# Main_Titan_V2.net
KiCad netlist of a schematic drawn in EAGLE
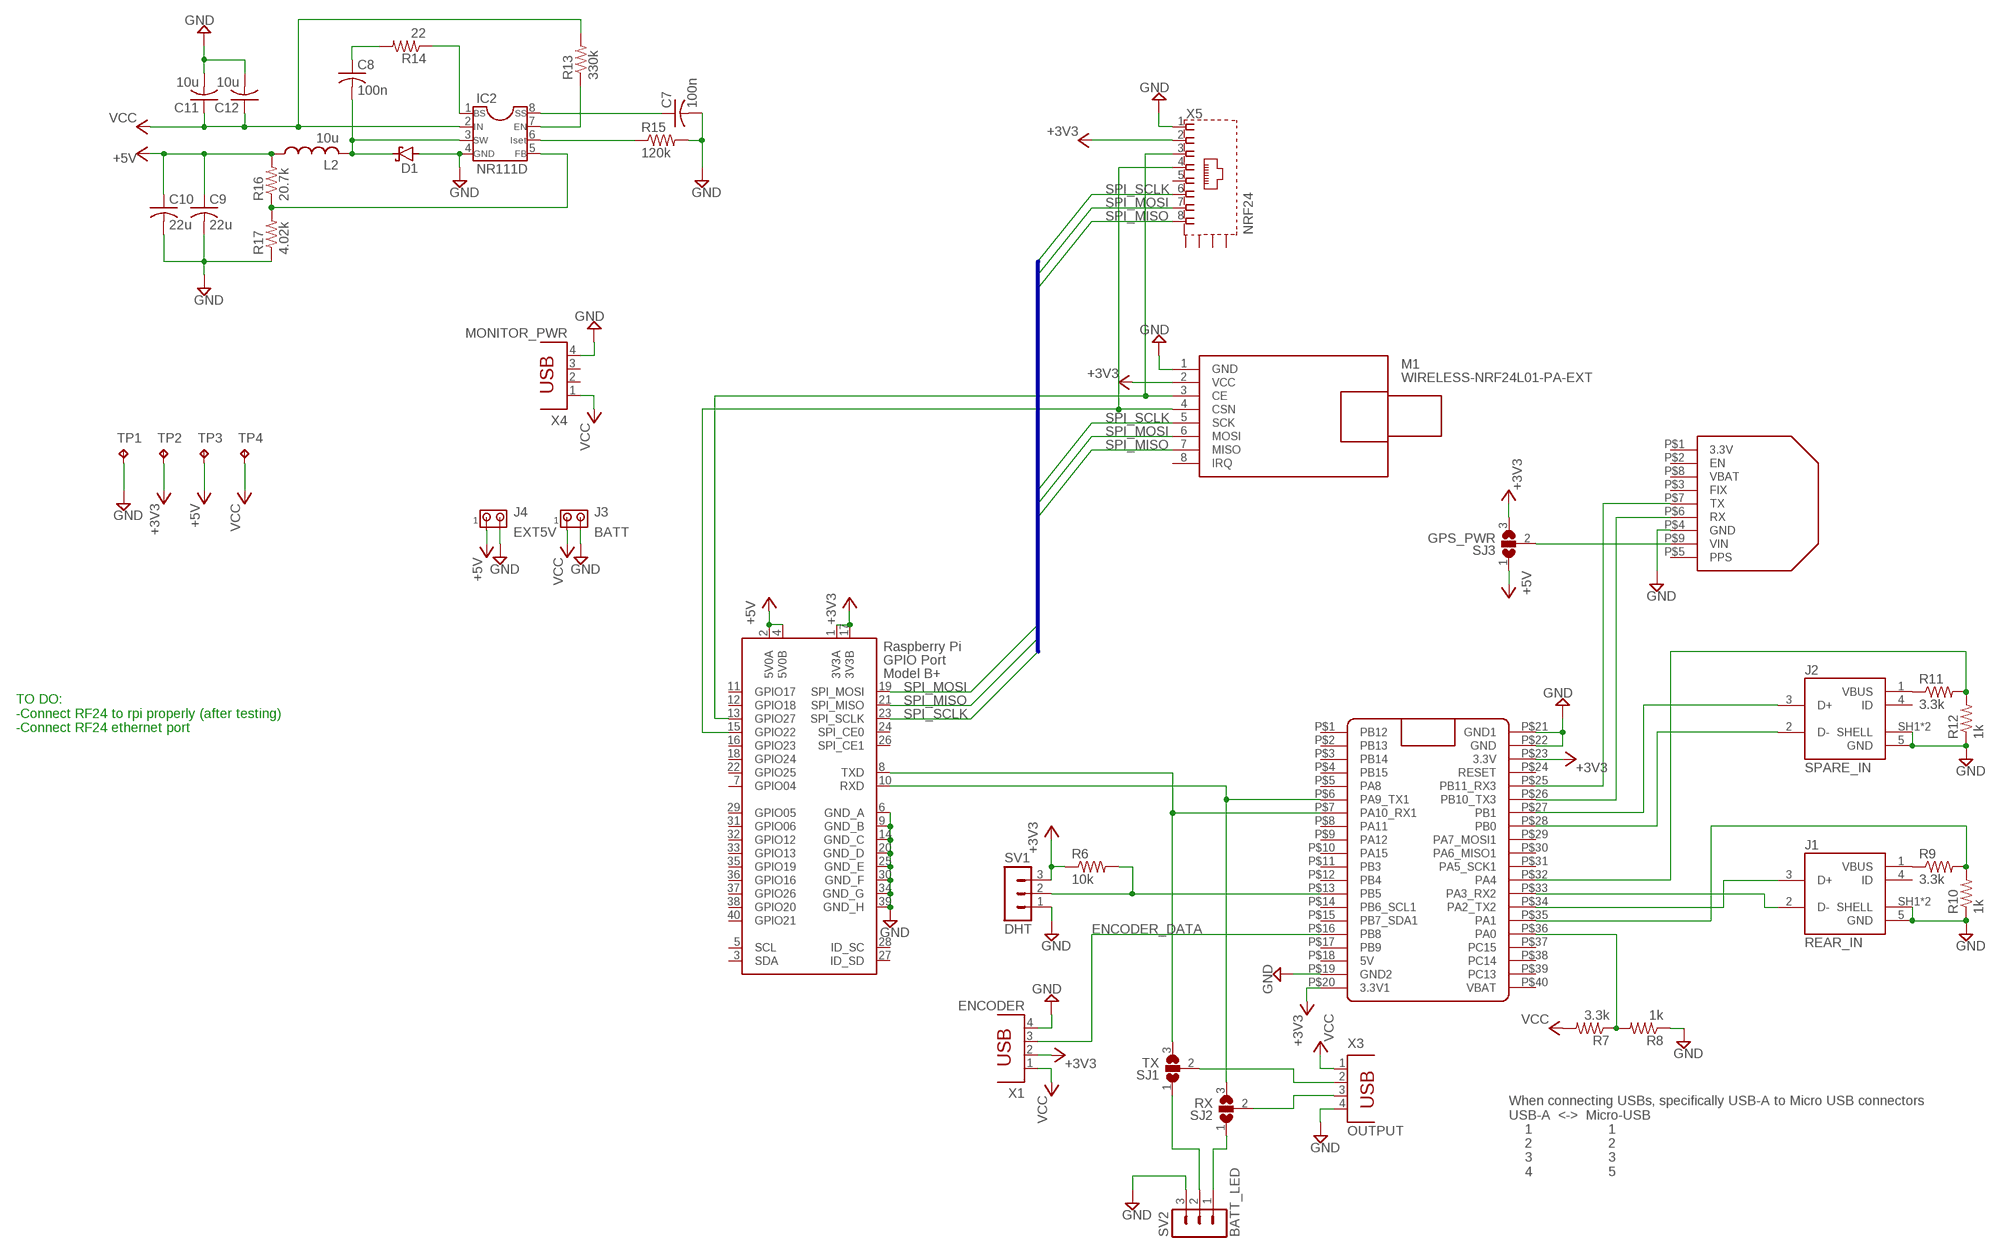
[diagram p0: schematic, sheet 1]

(export (version "E")
  (design (tool "Eeschema 10.0.6"))
  (components
    (comp (ref "C7")
      (value "100n")
      (footprint "eagle-import:C050-024X044")
      (libsource (lib "eagle-import") (part "C-US050-024X044"))
    )
    (comp (ref "C8")
      (value "100n")
      (footprint "eagle-import:C050-024X044")
      (libsource (lib "eagle-import") (part "C-US050-024X044"))
    )
    (comp (ref "C9")
      (value "22u")
      (footprint "eagle-import:C025-024X044")
      (libsource (lib "eagle-import") (part "C-US025-024X044"))
    )
    (comp (ref "C10")
      (value "22u")
      (footprint "eagle-import:C025-024X044")
      (libsource (lib "eagle-import") (part "C-US025-024X044"))
    )
    (comp (ref "C11")
      (value "10u")
      (footprint "eagle-import:C025-024X044")
      (libsource (lib "eagle-import") (part "C-US025-024X044"))
    )
    (comp (ref "C12")
      (value "10u")
      (footprint "eagle-import:C025-024X044")
      (libsource (lib "eagle-import") (part "C-US025-024X044"))
    )
    (comp (ref "D1")
      (value "SCHOTTKY-DIODEC4111-15")
      (footprint "eagle-import:C4111-15")
      (libsource (lib "eagle-import") (part "SCHOTTKY-DIODEC4111-15"))
    )
    (comp (ref "IC2")
      (value "NR111D")
      (footprint "eagle-import:DIL08")
      (libsource (lib "eagle-import") (part "DIL8"))
    )
    (comp (ref "J1")
      (value "REAR_IN")
      (footprint "eagle-import:TE_2172034-1")
      (fields
        (field (name "COMMENT") "2172034-1")
        (field (name "DIGI-KEY_PART_NUMBER") "A135698-ND")
        (field (name "MF") "TE Connectivity")
      )
      (libsource (lib "eagle-import") (part "2172034-1"))
    )
    (comp (ref "J2")
      (value "SPARE_IN")
      (footprint "eagle-import:TE_2172034-1")
      (fields
        (field (name "COMMENT") "2172034-1")
        (field (name "DIGI-KEY_PART_NUMBER") "A135698-ND")
        (field (name "MF") "TE Connectivity")
      )
      (libsource (lib "eagle-import") (part "2172034-1"))
    )
    (comp (ref "J3")
      (value "BATT")
      (footprint "eagle-import:1X2MTA")
      (libsource (lib "eagle-import") (part "MTA02-156"))
    )
    (comp (ref "J4")
      (value "EXT5V")
      (footprint "eagle-import:1X2MTA")
      (libsource (lib "eagle-import") (part "MTA02-156"))
    )
    (comp (ref "L2")
      (value "10u")
      (footprint "eagle-import:INDRD650W105D880H1100B")
      (libsource (lib "eagle-import") (part "WURTHINDUCTOR1"))
    )
    (comp (ref "M1")
      (value "WIRELESS-NRF24L01-PA-EXT")
      (footprint "eagle-import:WIRELESS-NRF24L01-PA-EXT")
      (libsource (lib "eagle-import") (part "WIRELESS-NRF24L01-PA-EXT"))
    )
    (comp (ref "R6")
      (value "10k")
      (footprint "eagle-import:0204_7")
      (libsource (lib "eagle-import") (part "R-US_0204/7"))
    )
    (comp (ref "R7")
      (value "3.3k")
      (footprint "eagle-import:0204_7")
      (libsource (lib "eagle-import") (part "R-US_0204/7"))
    )
    (comp (ref "R8")
      (value "1k")
      (footprint "eagle-import:0204_7")
      (libsource (lib "eagle-import") (part "R-US_0204/7"))
    )
    (comp (ref "R9")
      (value "3.3k")
      (footprint "eagle-import:0204_7")
      (libsource (lib "eagle-import") (part "R-US_0204/7"))
    )
    (comp (ref "R10")
      (value "1k")
      (footprint "eagle-import:0204_7")
      (libsource (lib "eagle-import") (part "R-US_0204/7"))
    )
    (comp (ref "R11")
      (value "3.3k")
      (footprint "eagle-import:0204_7")
      (libsource (lib "eagle-import") (part "R-US_0204/7"))
    )
    (comp (ref "R12")
      (value "1k")
      (footprint "eagle-import:0204_7")
      (libsource (lib "eagle-import") (part "R-US_0204/7"))
    )
    (comp (ref "R13")
      (value "330k")
      (footprint "eagle-import:0204_7")
      (libsource (lib "eagle-import") (part "R-US_0204/7"))
    )
    (comp (ref "R14")
      (value "22")
      (footprint "eagle-import:0204_7")
      (libsource (lib "eagle-import") (part "R-US_0204/7"))
    )
    (comp (ref "R15")
      (value "120k")
      (footprint "eagle-import:0204_7")
      (libsource (lib "eagle-import") (part "R-US_0204/7"))
    )
    (comp (ref "R16")
      (value "20.7k")
      (footprint "eagle-import:0204_7")
      (libsource (lib "eagle-import") (part "R-US_0204/7"))
    )
    (comp (ref "R17")
      (value "4.02k")
      (footprint "eagle-import:0204_7")
      (libsource (lib "eagle-import") (part "R-US_0204/7"))
    )
    (comp (ref "SJ1")
      (value "TX")
      (footprint "eagle-import:SJ_2")
      (libsource (lib "eagle-import") (part "SJ2W"))
    )
    (comp (ref "SJ2")
      (value "RX")
      (footprint "eagle-import:SJ_2")
      (libsource (lib "eagle-import") (part "SJ2W"))
    )
    (comp (ref "SJ3")
      (value "GPS_PWR")
      (footprint "eagle-import:SJ_2")
      (libsource (lib "eagle-import") (part "SJ2W"))
    )
    (comp (ref "SV1")
      (value "DHT")
      (footprint "eagle-import:MA03-1")
      (libsource (lib "eagle-import") (part "MA03-1"))
    )
    (comp (ref "SV2")
      (value "BATT_LED")
      (footprint "eagle-import:MA03-1")
      (libsource (lib "eagle-import") (part "MA03-1"))
    )
    (comp (ref "TP1")
      (value "GND")
      (footprint "eagle-import:TP20SQ")
      (libsource (lib "eagle-import") (part "TPTP20SQ"))
    )
    (comp (ref "TP2")
      (value "3V3")
      (footprint "eagle-import:TP20SQ")
      (libsource (lib "eagle-import") (part "TPTP20SQ"))
    )
    (comp (ref "TP3")
      (value "5V")
      (footprint "eagle-import:TP20SQ")
      (libsource (lib "eagle-import") (part "TPTP20SQ"))
    )
    (comp (ref "TP4")
      (value "BAT")
      (footprint "eagle-import:TP20SQ")
      (libsource (lib "eagle-import") (part "TPTP20SQ"))
    )
    (comp (ref "U$1")
      (value "BLUE_PILL")
      (footprint "eagle-import:BLUE_PILL")
      (libsource (lib "eagle-import") (part "BLUE_PILL"))
    )
    (comp (ref "U$3")
      (value "ULTIMATE-GPS")
      (footprint "eagle-import:ULTIMATE_GPS")
      (libsource (lib "eagle-import") (part "ULTIMATE-GPS"))
    )
    (comp (ref "X1")
      (value "ENCODER")
      (footprint "eagle-import:PN87520")
      (libsource (lib "eagle-import") (part "PN87520"))
    )
    (comp (ref "X2")
      (value "RPI")
      (footprint "eagle-import:RASPI_GPIO_B+_BOX")
      (libsource (lib "eagle-import") (part "RASPI_GPIO_B+#_BOX"))
    )
    (comp (ref "X3")
      (value "OUTPUT")
      (footprint "eagle-import:PN87520")
      (libsource (lib "eagle-import") (part "PN87520"))
    )
    (comp (ref "X4")
      (value "MONITOR_PWR")
      (footprint "eagle-import:PN87520")
      (libsource (lib "eagle-import") (part "PN87520"))
    )
    (comp (ref "X5")
      (value "NRF24")
      (footprint "eagle-import:RJ45-SHIELD1")
      (libsource (lib "eagle-import") (part "RJ4521-S-6L"))
    )
  )
  (nets
    (net (code "1") (name "+3V3") (class "Default")
      (node (ref "M1") (pin "2") (pinfunction "VCC_2") (pintype "power_in"))
      (node (ref "R6") (pin "1") (pinfunction "1_1") (pintype "passive"))
      (node (ref "SJ3") (pin "3") (pinfunction "3_3") (pintype "passive"))
      (node (ref "SV1") (pin "3") (pinfunction "3_3") (pintype "passive"))
      (node (ref "TP2") (pin "TP") (pinfunction "TP_TP") (pintype "input"))
      (node (ref "U$1") (pin "P$20") (pinfunction "3.3V1_P$20") (pintype "power_in"))
      (node (ref "U$1") (pin "P$23") (pinfunction "3.3V_P$23") (pintype "power_in"))
      (node (ref "X1") (pin "2") (pinfunction "2_2") (pintype "passive"))
      (node (ref "X2") (pin "1") (pinfunction "3V3A_1") (pintype "power_in"))
      (node (ref "X2") (pin "17") (pinfunction "3V3B_17") (pintype "power_in"))
      (node (ref "X5") (pin "2") (pinfunction "2_2") (pintype "passive"))
    )
    (net (code "2") (name "+5V") (class "Default")
      (node (ref "C10") (pin "1") (pinfunction "1_1") (pintype "passive"))
      (node (ref "C9") (pin "1") (pinfunction "1_1") (pintype "passive"))
      (node (ref "J4") (pin "1") (pinfunction "1_1") (pintype "passive"))
      (node (ref "L2") (pin "1") (pinfunction "1_1") (pintype "passive"))
      (node (ref "R16") (pin "2") (pinfunction "2_2") (pintype "passive"))
      (node (ref "SJ3") (pin "1") (pinfunction "1_1") (pintype "passive"))
      (node (ref "TP3") (pin "TP") (pinfunction "TP_TP") (pintype "input"))
      (node (ref "X2") (pin "2") (pinfunction "5V0A_2") (pintype "power_in"))
      (node (ref "X2") (pin "4") (pinfunction "5V0B_4") (pintype "power_in"))
    )
    (net (code "3") (name "/3.3V") (class "Default")
      (node (ref "U$3") (pin "P$1") (pinfunction "3.3V_P$1") (pintype "power_in"))
    )
    (net (code "4") (name "/ENCODER_DATA") (class "Default")
      (node (ref "U$1") (pin "P$16") (pinfunction "PB8_P$16") (pintype "bidirectional"))
      (node (ref "X1") (pin "3") (pinfunction "3_3") (pintype "passive"))
    )
    (net (code "5") (name "/SPI_MISO") (class "Default")
      (node (ref "M1") (pin "7") (pinfunction "MISO_7") (pintype "bidirectional"))
      (node (ref "X2") (pin "21") (pinfunction "SPI_MISO_21") (pintype "bidirectional"))
      (node (ref "X5") (pin "8") (pinfunction "8_8") (pintype "passive"))
    )
    (net (code "6") (name "/SPI_MOSI") (class "Default")
      (node (ref "M1") (pin "6") (pinfunction "MOSI_6") (pintype "bidirectional"))
      (node (ref "X2") (pin "19") (pinfunction "SPI_MOSI_19") (pintype "bidirectional"))
      (node (ref "X5") (pin "7") (pinfunction "7_7") (pintype "passive"))
    )
    (net (code "7") (name "/SPI_SCLK") (class "Default")
      (node (ref "M1") (pin "5") (pinfunction "SCK_5") (pintype "bidirectional"))
      (node (ref "X2") (pin "23") (pinfunction "SPI_SCLK_23") (pintype "bidirectional"))
      (node (ref "X5") (pin "6") (pinfunction "6_6") (pintype "passive"))
    )
    (net (code "8") (name "GND") (class "Default")
      (node (ref "C10") (pin "2") (pinfunction "2_2") (pintype "passive"))
      (node (ref "C11") (pin "2") (pinfunction "2_2") (pintype "passive"))
      (node (ref "C12") (pin "2") (pinfunction "2_2") (pintype "passive"))
      (node (ref "C7") (pin "2") (pinfunction "2_2") (pintype "passive"))
      (node (ref "C9") (pin "2") (pinfunction "2_2") (pintype "passive"))
      (node (ref "D1") (pin "A") (pinfunction "A_A") (pintype "passive"))
      (node (ref "IC2") (pin "4") (pinfunction "GND_4") (pintype "passive"))
      (node (ref "J1") (pin "5") (pinfunction "GND_5") (pintype "power_in"))
      (node (ref "J1") (pin "SH1") (pinfunction "SHELL_SH1") (pintype "power_in"))
      (node (ref "J1") (pin "SH2") (pinfunction "SHELL_SH2") (pintype "power_in"))
      (node (ref "J2") (pin "5") (pinfunction "GND_5") (pintype "power_in"))
      (node (ref "J2") (pin "SH1") (pinfunction "SHELL_SH1") (pintype "power_in"))
      (node (ref "J2") (pin "SH2") (pinfunction "SHELL_SH2") (pintype "power_in"))
      (node (ref "J3") (pin "2") (pinfunction "2_2") (pintype "passive"))
      (node (ref "J4") (pin "2") (pinfunction "2_2") (pintype "passive"))
      (node (ref "M1") (pin "1") (pinfunction "GND_1") (pintype "power_in"))
      (node (ref "R10") (pin "1") (pinfunction "1_1") (pintype "passive"))
      (node (ref "R12") (pin "1") (pinfunction "1_1") (pintype "passive"))
      (node (ref "R15") (pin "2") (pinfunction "2_2") (pintype "passive"))
      (node (ref "R17") (pin "1") (pinfunction "1_1") (pintype "passive"))
      (node (ref "R8") (pin "1") (pinfunction "1_1") (pintype "passive"))
      (node (ref "SV1") (pin "1") (pinfunction "1_1") (pintype "passive"))
      (node (ref "SV2") (pin "3") (pinfunction "3_3") (pintype "passive"))
      (node (ref "TP1") (pin "TP") (pinfunction "TP_TP") (pintype "input"))
      (node (ref "U$1") (pin "P$19") (pinfunction "GND2_P$19") (pintype "bidirectional"))
      (node (ref "U$1") (pin "P$21") (pinfunction "GND1_P$21") (pintype "power_in"))
      (node (ref "U$1") (pin "P$22") (pinfunction "GND_P$22") (pintype "bidirectional"))
      (node (ref "U$3") (pin "P$4") (pinfunction "GND_P$4") (pintype "power_in"))
      (node (ref "X1") (pin "4") (pinfunction "4_4") (pintype "passive"))
      (node (ref "X2") (pin "14") (pinfunction "GND_C_14") (pintype "power_in"))
      (node (ref "X2") (pin "20") (pinfunction "GND_D_20") (pintype "power_in"))
      (node (ref "X2") (pin "25") (pinfunction "GND_E_25") (pintype "power_in"))
      (node (ref "X2") (pin "30") (pinfunction "GND_F_30") (pintype "power_in"))
      (node (ref "X2") (pin "34") (pinfunction "GND_G_34") (pintype "power_in"))
      (node (ref "X2") (pin "39") (pinfunction "GND_H_39") (pintype "power_in"))
      (node (ref "X2") (pin "6") (pinfunction "GND_A_6") (pintype "power_in"))
      (node (ref "X2") (pin "9") (pinfunction "GND_B_9") (pintype "power_in"))
      (node (ref "X3") (pin "4") (pinfunction "4_4") (pintype "passive"))
      (node (ref "X4") (pin "4") (pinfunction "4_4") (pintype "passive"))
      (node (ref "X5") (pin "1") (pinfunction "1_1") (pintype "passive"))
    )
    (net (code "9") (name "Net-(C8-Pad1)") (class "Default")
      (node (ref "C8") (pin "1") (pinfunction "1_1") (pintype "passive"))
      (node (ref "R14") (pin "2") (pinfunction "2_2") (pintype "passive"))
    )
    (net (code "10") (name "Net-(IC2-BS)") (class "Default")
      (node (ref "IC2") (pin "1") (pinfunction "BS_1") (pintype "passive"))
      (node (ref "R14") (pin "1") (pinfunction "1_1") (pintype "passive"))
    )
    (net (code "11") (name "Net-(IC2-EN)") (class "Default")
      (node (ref "IC2") (pin "7") (pinfunction "EN_7") (pintype "passive"))
      (node (ref "R13") (pin "1") (pinfunction "1_1") (pintype "passive"))
    )
    (net (code "12") (name "Net-(IC2-FB)") (class "Default")
      (node (ref "IC2") (pin "5") (pinfunction "FB_5") (pintype "passive"))
      (node (ref "R16") (pin "1") (pinfunction "1_1") (pintype "passive"))
      (node (ref "R17") (pin "2") (pinfunction "2_2") (pintype "passive"))
    )
    (net (code "13") (name "Net-(IC2-ISET)") (class "Default")
      (node (ref "IC2") (pin "6") (pinfunction "ISET_6") (pintype "passive"))
      (node (ref "R15") (pin "1") (pinfunction "1_1") (pintype "passive"))
    )
    (net (code "14") (name "Net-(IC2-SS)") (class "Default")
      (node (ref "C7") (pin "1") (pinfunction "1_1") (pintype "passive"))
      (node (ref "IC2") (pin "8") (pinfunction "SS_8") (pintype "passive"))
    )
    (net (code "15") (name "Net-(IC2-SW)") (class "Default")
      (node (ref "C8") (pin "2") (pinfunction "2_2") (pintype "passive"))
      (node (ref "D1") (pin "C") (pinfunction "C_C") (pintype "passive"))
      (node (ref "IC2") (pin "3") (pinfunction "SW_3") (pintype "passive"))
      (node (ref "L2") (pin "2") (pinfunction "2_2") (pintype "passive"))
    )
    (net (code "16") (name "Net-(J1-D+)") (class "Default")
      (node (ref "J1") (pin "3") (pinfunction "D+_3") (pintype "bidirectional"))
      (node (ref "U$1") (pin "P$34") (pinfunction "PA2_TX2_P$34") (pintype "bidirectional"))
    )
    (net (code "17") (name "Net-(J1-D-)") (class "Default")
      (node (ref "J1") (pin "2") (pinfunction "D-_2") (pintype "bidirectional"))
      (node (ref "U$1") (pin "P$33") (pinfunction "PA3_RX2_P$33") (pintype "bidirectional"))
    )
    (net (code "18") (name "Net-(J1-VBUS)") (class "Default")
      (node (ref "J1") (pin "1") (pinfunction "VBUS_1") (pintype "power_in"))
      (node (ref "R9") (pin "1") (pinfunction "1_1") (pintype "passive"))
    )
    (net (code "19") (name "Net-(J2-D+)") (class "Default")
      (node (ref "J2") (pin "3") (pinfunction "D+_3") (pintype "bidirectional"))
      (node (ref "U$1") (pin "P$27") (pinfunction "PB1_P$27") (pintype "bidirectional"))
    )
    (net (code "20") (name "Net-(J2-D-)") (class "Default")
      (node (ref "J2") (pin "2") (pinfunction "D-_2") (pintype "bidirectional"))
      (node (ref "U$1") (pin "P$28") (pinfunction "PB0_P$28") (pintype "bidirectional"))
    )
    (net (code "21") (name "Net-(J2-VBUS)") (class "Default")
      (node (ref "J2") (pin "1") (pinfunction "VBUS_1") (pintype "power_in"))
      (node (ref "R11") (pin "1") (pinfunction "1_1") (pintype "passive"))
    )
    (net (code "22") (name "Net-(M1-CE)") (class "Default")
      (node (ref "M1") (pin "3") (pinfunction "CE_3") (pintype "bidirectional"))
      (node (ref "X2") (pin "13") (pinfunction "GPIO27_13") (pintype "bidirectional"))
      (node (ref "X5") (pin "3") (pinfunction "3_3") (pintype "passive"))
    )
    (net (code "23") (name "Net-(M1-CSN)") (class "Default")
      (node (ref "M1") (pin "4") (pinfunction "CSN_4") (pintype "bidirectional"))
      (node (ref "X2") (pin "15") (pinfunction "GPIO22_15") (pintype "bidirectional"))
      (node (ref "X5") (pin "4") (pinfunction "4_4") (pintype "passive"))
    )
    (net (code "24") (name "Net-(SJ1-Pad1)") (class "Default")
      (node (ref "SJ1") (pin "1") (pinfunction "1_1") (pintype "passive"))
      (node (ref "SV2") (pin "2") (pinfunction "2_2") (pintype "passive"))
    )
    (net (code "25") (name "Net-(SJ1-Pad2)") (class "Default")
      (node (ref "SJ1") (pin "2") (pinfunction "2_2") (pintype "passive"))
      (node (ref "X3") (pin "2") (pinfunction "2_2") (pintype "passive"))
    )
    (net (code "26") (name "Net-(SJ2-Pad1)") (class "Default")
      (node (ref "SJ2") (pin "1") (pinfunction "1_1") (pintype "passive"))
      (node (ref "SV2") (pin "1") (pinfunction "1_1") (pintype "passive"))
    )
    (net (code "27") (name "Net-(SJ2-Pad2)") (class "Default")
      (node (ref "SJ2") (pin "2") (pinfunction "2_2") (pintype "passive"))
      (node (ref "X3") (pin "3") (pinfunction "3_3") (pintype "passive"))
    )
    (net (code "28") (name "Net-(U$1-PA0)") (class "Default")
      (node (ref "R7") (pin "1") (pinfunction "1_1") (pintype "passive"))
      (node (ref "R8") (pin "2") (pinfunction "2_2") (pintype "passive"))
      (node (ref "U$1") (pin "P$36") (pinfunction "PA0_P$36") (pintype "bidirectional"))
    )
    (net (code "29") (name "Net-(U$1-PA1)") (class "Default")
      (node (ref "R10") (pin "2") (pinfunction "2_2") (pintype "passive"))
      (node (ref "R9") (pin "2") (pinfunction "2_2") (pintype "passive"))
      (node (ref "U$1") (pin "P$35") (pinfunction "PA1_P$35") (pintype "bidirectional"))
    )
    (net (code "30") (name "Net-(U$1-PA4)") (class "Default")
      (node (ref "R11") (pin "2") (pinfunction "2_2") (pintype "passive"))
      (node (ref "R12") (pin "2") (pinfunction "2_2") (pintype "passive"))
      (node (ref "U$1") (pin "P$32") (pinfunction "PA4_P$32") (pintype "bidirectional"))
    )
    (net (code "31") (name "Net-(U$1-PA9_TX1)") (class "Default")
      (node (ref "SJ2") (pin "3") (pinfunction "3_3") (pintype "passive"))
      (node (ref "U$1") (pin "P$6") (pinfunction "PA9_TX1_P$6") (pintype "bidirectional"))
      (node (ref "X2") (pin "10") (pinfunction "RXD_10") (pintype "bidirectional"))
    )
    (net (code "32") (name "Net-(U$1-PA10_RX1)") (class "Default")
      (node (ref "SJ1") (pin "3") (pinfunction "3_3") (pintype "passive"))
      (node (ref "U$1") (pin "P$7") (pinfunction "PA10_RX1_P$7") (pintype "bidirectional"))
      (node (ref "X2") (pin "8") (pinfunction "TXD_8") (pintype "bidirectional"))
    )
    (net (code "33") (name "Net-(U$1-PB5)") (class "Default")
      (node (ref "R6") (pin "2") (pinfunction "2_2") (pintype "passive"))
      (node (ref "SV1") (pin "2") (pinfunction "2_2") (pintype "passive"))
      (node (ref "U$1") (pin "P$13") (pinfunction "PB5_P$13") (pintype "bidirectional"))
    )
    (net (code "34") (name "Net-(U$1-PB10_TX3)") (class "Default")
      (node (ref "U$1") (pin "P$26") (pinfunction "PB10_TX3_P$26") (pintype "bidirectional"))
      (node (ref "U$3") (pin "P$6") (pinfunction "RX_P$6") (pintype "bidirectional"))
    )
    (net (code "35") (name "Net-(U$1-PB11_RX3)") (class "Default")
      (node (ref "U$1") (pin "P$25") (pinfunction "PB11_RX3_P$25") (pintype "bidirectional"))
      (node (ref "U$3") (pin "P$7") (pinfunction "TX_P$7") (pintype "bidirectional"))
    )
    (net (code "36") (name "Net-(U$3-VIN)") (class "Default")
      (node (ref "SJ3") (pin "2") (pinfunction "2_2") (pintype "passive"))
      (node (ref "U$3") (pin "P$9") (pinfunction "VIN_P$9") (pintype "bidirectional"))
    )
    (net (code "37") (name "VCC") (class "Default")
      (node (ref "C11") (pin "1") (pinfunction "1_1") (pintype "passive"))
      (node (ref "C12") (pin "1") (pinfunction "1_1") (pintype "passive"))
      (node (ref "IC2") (pin "2") (pinfunction "IN_2") (pintype "passive"))
      (node (ref "J3") (pin "1") (pinfunction "1_1") (pintype "passive"))
      (node (ref "R13") (pin "2") (pinfunction "2_2") (pintype "passive"))
      (node (ref "R7") (pin "2") (pinfunction "2_2") (pintype "passive"))
      (node (ref "TP4") (pin "TP") (pinfunction "TP_TP") (pintype "input"))
      (node (ref "X1") (pin "1") (pinfunction "1_1") (pintype "passive"))
      (node (ref "X3") (pin "1") (pinfunction "1_1") (pintype "passive"))
      (node (ref "X4") (pin "1") (pinfunction "1_1") (pintype "passive"))
    )
    (net (code "38") (name "unconnected-(J1-ID-Pad4)") (class "Default")
      (node (ref "J1") (pin "4") (pinfunction "ID_4") (pintype "passive"))
    )
    (net (code "39") (name "unconnected-(J2-ID-Pad4)") (class "Default")
      (node (ref "J2") (pin "4") (pinfunction "ID_4") (pintype "passive"))
    )
    (net (code "40") (name "unconnected-(M1-IRQ-Pad8)") (class "Default")
      (node (ref "M1") (pin "8") (pinfunction "IRQ_8") (pintype "bidirectional"))
    )
    (net (code "41") (name "unconnected-(U$1-5V-PadP$18)") (class "Default")
      (node (ref "U$1") (pin "P$18") (pinfunction "5V_P$18") (pintype "bidirectional"))
    )
    (net (code "42") (name "unconnected-(U$1-PA5_SCK1-PadP$31)") (class "Default")
      (node (ref "U$1") (pin "P$31") (pinfunction "PA5_SCK1_P$31") (pintype "bidirectional"))
    )
    (net (code "43") (name "unconnected-(U$1-PA6_MISO1-PadP$30)") (class "Default")
      (node (ref "U$1") (pin "P$30") (pinfunction "PA6_MISO1_P$30") (pintype "bidirectional"))
    )
    (net (code "44") (name "unconnected-(U$1-PA7_MOSI1-PadP$29)") (class "Default")
      (node (ref "U$1") (pin "P$29") (pinfunction "PA7_MOSI1_P$29") (pintype "bidirectional"))
    )
    (net (code "45") (name "unconnected-(U$1-PA8-PadP$5)") (class "Default")
      (node (ref "U$1") (pin "P$5") (pinfunction "PA8_P$5") (pintype "bidirectional"))
    )
    (net (code "46") (name "unconnected-(U$1-PA11-PadP$8)") (class "Default")
      (node (ref "U$1") (pin "P$8") (pinfunction "PA11_P$8") (pintype "bidirectional"))
    )
    (net (code "47") (name "unconnected-(U$1-PA12-PadP$9)") (class "Default")
      (node (ref "U$1") (pin "P$9") (pinfunction "PA12_P$9") (pintype "bidirectional"))
    )
    (net (code "48") (name "unconnected-(U$1-PA15-PadP$10)") (class "Default")
      (node (ref "U$1") (pin "P$10") (pinfunction "PA15_P$10") (pintype "bidirectional"))
    )
    (net (code "49") (name "unconnected-(U$1-PB3-PadP$11)") (class "Default")
      (node (ref "U$1") (pin "P$11") (pinfunction "PB3_P$11") (pintype "bidirectional"))
    )
    (net (code "50") (name "unconnected-(U$1-PB4-PadP$12)") (class "Default")
      (node (ref "U$1") (pin "P$12") (pinfunction "PB4_P$12") (pintype "bidirectional"))
    )
    (net (code "51") (name "unconnected-(U$1-PB6_SCL1-PadP$14)") (class "Default")
      (node (ref "U$1") (pin "P$14") (pinfunction "PB6_SCL1_P$14") (pintype "bidirectional"))
    )
    (net (code "52") (name "unconnected-(U$1-PB7_SDA1-PadP$15)") (class "Default")
      (node (ref "U$1") (pin "P$15") (pinfunction "PB7_SDA1_P$15") (pintype "bidirectional"))
    )
    (net (code "53") (name "unconnected-(U$1-PB9-PadP$17)") (class "Default")
      (node (ref "U$1") (pin "P$17") (pinfunction "PB9_P$17") (pintype "bidirectional"))
    )
    (net (code "54") (name "unconnected-(U$1-PB12-PadP$1)") (class "Default")
      (node (ref "U$1") (pin "P$1") (pinfunction "PB12_P$1") (pintype "bidirectional"))
    )
    (net (code "55") (name "unconnected-(U$1-PB13-PadP$2)") (class "Default")
      (node (ref "U$1") (pin "P$2") (pinfunction "PB13_P$2") (pintype "bidirectional"))
    )
    (net (code "56") (name "unconnected-(U$1-PB14-PadP$3)") (class "Default")
      (node (ref "U$1") (pin "P$3") (pinfunction "PB14_P$3") (pintype "bidirectional"))
    )
    (net (code "57") (name "unconnected-(U$1-PB15-PadP$4)") (class "Default")
      (node (ref "U$1") (pin "P$4") (pinfunction "PB15_P$4") (pintype "bidirectional"))
    )
    (net (code "58") (name "unconnected-(U$1-PC13-PadP$39)") (class "Default")
      (node (ref "U$1") (pin "P$39") (pinfunction "PC13_P$39") (pintype "bidirectional"))
    )
    (net (code "59") (name "unconnected-(U$1-PC14-PadP$38)") (class "Default")
      (node (ref "U$1") (pin "P$38") (pinfunction "PC14_P$38") (pintype "bidirectional"))
    )
    (net (code "60") (name "unconnected-(U$1-PC15-PadP$37)") (class "Default")
      (node (ref "U$1") (pin "P$37") (pinfunction "PC15_P$37") (pintype "bidirectional"))
    )
    (net (code "61") (name "unconnected-(U$1-RESET-PadP$24)") (class "Default")
      (node (ref "U$1") (pin "P$24") (pinfunction "RESET_P$24") (pintype "bidirectional"))
    )
    (net (code "62") (name "unconnected-(U$1-VBAT-PadP$40)") (class "Default")
      (node (ref "U$1") (pin "P$40") (pinfunction "VBAT_P$40") (pintype "bidirectional"))
    )
    (net (code "63") (name "unconnected-(U$3-EN-PadP$2)") (class "Default")
      (node (ref "U$3") (pin "P$2") (pinfunction "EN_P$2") (pintype "bidirectional"))
    )
    (net (code "64") (name "unconnected-(U$3-FIX-PadP$3)") (class "Default")
      (node (ref "U$3") (pin "P$3") (pinfunction "FIX_P$3") (pintype "bidirectional"))
    )
    (net (code "65") (name "unconnected-(U$3-PPS-PadP$5)") (class "Default")
      (node (ref "U$3") (pin "P$5") (pinfunction "PPS_P$5") (pintype "bidirectional"))
    )
    (net (code "66") (name "unconnected-(U$3-VBAT-PadP$8)") (class "Default")
      (node (ref "U$3") (pin "P$8") (pinfunction "VBAT_P$8") (pintype "bidirectional"))
    )
    (net (code "67") (name "unconnected-(X2-GPIO04-Pad7)") (class "Default")
      (node (ref "X2") (pin "7") (pinfunction "GPIO04_7") (pintype "bidirectional"))
    )
    (net (code "68") (name "unconnected-(X2-GPIO05-Pad29)") (class "Default")
      (node (ref "X2") (pin "29") (pinfunction "GPIO05_29") (pintype "no_connect"))
    )
    (net (code "69") (name "unconnected-(X2-GPIO06-Pad31)") (class "Default")
      (node (ref "X2") (pin "31") (pinfunction "GPIO06_31") (pintype "no_connect"))
    )
    (net (code "70") (name "unconnected-(X2-GPIO12-Pad32)") (class "Default")
      (node (ref "X2") (pin "32") (pinfunction "GPIO12_32") (pintype "no_connect"))
    )
    (net (code "71") (name "unconnected-(X2-GPIO13-Pad33)") (class "Default")
      (node (ref "X2") (pin "33") (pinfunction "GPIO13_33") (pintype "no_connect"))
    )
    (net (code "72") (name "unconnected-(X2-GPIO16-Pad36)") (class "Default")
      (node (ref "X2") (pin "36") (pinfunction "GPIO16_36") (pintype "no_connect"))
    )
    (net (code "73") (name "unconnected-(X2-GPIO17-Pad11)") (class "Default")
      (node (ref "X2") (pin "11") (pinfunction "GPIO17_11") (pintype "bidirectional"))
    )
    (net (code "74") (name "unconnected-(X2-GPIO18-Pad12)") (class "Default")
      (node (ref "X2") (pin "12") (pinfunction "GPIO18_12") (pintype "bidirectional"))
    )
    (net (code "75") (name "unconnected-(X2-GPIO19-Pad35)") (class "Default")
      (node (ref "X2") (pin "35") (pinfunction "GPIO19_35") (pintype "no_connect"))
    )
    (net (code "76") (name "unconnected-(X2-GPIO20-Pad38)") (class "Default")
      (node (ref "X2") (pin "38") (pinfunction "GPIO20_38") (pintype "no_connect"))
    )
    (net (code "77") (name "unconnected-(X2-GPIO21-Pad40)") (class "Default")
      (node (ref "X2") (pin "40") (pinfunction "GPIO21_40") (pintype "no_connect"))
    )
    (net (code "78") (name "unconnected-(X2-GPIO23-Pad16)") (class "Default")
      (node (ref "X2") (pin "16") (pinfunction "GPIO23_16") (pintype "bidirectional"))
    )
    (net (code "79") (name "unconnected-(X2-GPIO24-Pad18)") (class "Default")
      (node (ref "X2") (pin "18") (pinfunction "GPIO24_18") (pintype "bidirectional"))
    )
    (net (code "80") (name "unconnected-(X2-GPIO25-Pad22)") (class "Default")
      (node (ref "X2") (pin "22") (pinfunction "GPIO25_22") (pintype "bidirectional"))
    )
    (net (code "81") (name "unconnected-(X2-GPIO26-Pad37)") (class "Default")
      (node (ref "X2") (pin "37") (pinfunction "GPIO26_37") (pintype "no_connect"))
    )
    (net (code "82") (name "unconnected-(X2-ID_SC-Pad28)") (class "Default")
      (node (ref "X2") (pin "28") (pinfunction "ID_SC_28") (pintype "no_connect"))
    )
    (net (code "83") (name "unconnected-(X2-ID_SD-Pad27)") (class "Default")
      (node (ref "X2") (pin "27") (pinfunction "ID_SD_27") (pintype "no_connect"))
    )
    (net (code "84") (name "unconnected-(X2-SCL-Pad5)") (class "Default")
      (node (ref "X2") (pin "5") (pinfunction "SCL_5") (pintype "bidirectional"))
    )
    (net (code "85") (name "unconnected-(X2-SDA-Pad3)") (class "Default")
      (node (ref "X2") (pin "3") (pinfunction "SDA_3") (pintype "bidirectional"))
    )
    (net (code "86") (name "unconnected-(X2-SPI_CE0-Pad24)") (class "Default")
      (node (ref "X2") (pin "24") (pinfunction "SPI_CE0_24") (pintype "bidirectional"))
    )
    (net (code "87") (name "unconnected-(X2-SPI_CE1-Pad26)") (class "Default")
      (node (ref "X2") (pin "26") (pinfunction "SPI_CE1_26") (pintype "bidirectional"))
    )
    (net (code "88") (name "unconnected-(X4-Pad2)") (class "Default")
      (node (ref "X4") (pin "2") (pinfunction "2_2") (pintype "passive"))
    )
    (net (code "89") (name "unconnected-(X4-Pad3)") (class "Default")
      (node (ref "X4") (pin "3") (pinfunction "3_3") (pintype "passive"))
    )
    (net (code "90") (name "unconnected-(X5-Pad5)") (class "Default")
      (node (ref "X5") (pin "5") (pinfunction "5_5") (pintype "passive"))
    )
    (net (code "91") (name "unconnected-(X5-S-PadS1)") (class "Default")
      (node (ref "X5") (pin "S1") (pinfunction "S_S1") (pintype "passive"))
    )
    (net (code "92") (name "unconnected-(X5-S-PadS2)") (class "Default")
      (node (ref "X5") (pin "S2") (pinfunction "S_S2") (pintype "passive"))
    )
    (net (code "93") (name "unconnected-(X5-S-PadS3)") (class "Default")
      (node (ref "X5") (pin "S3") (pinfunction "S_S3") (pintype "passive"))
    )
    (net (code "94") (name "unconnected-(X5-S-PadS4)") (class "Default")
      (node (ref "X5") (pin "S4") (pinfunction "S_S4") (pintype "passive"))
    )
  )
)
